# Amp.net
KiCad netlist of a schematic drawn in Altium Designer
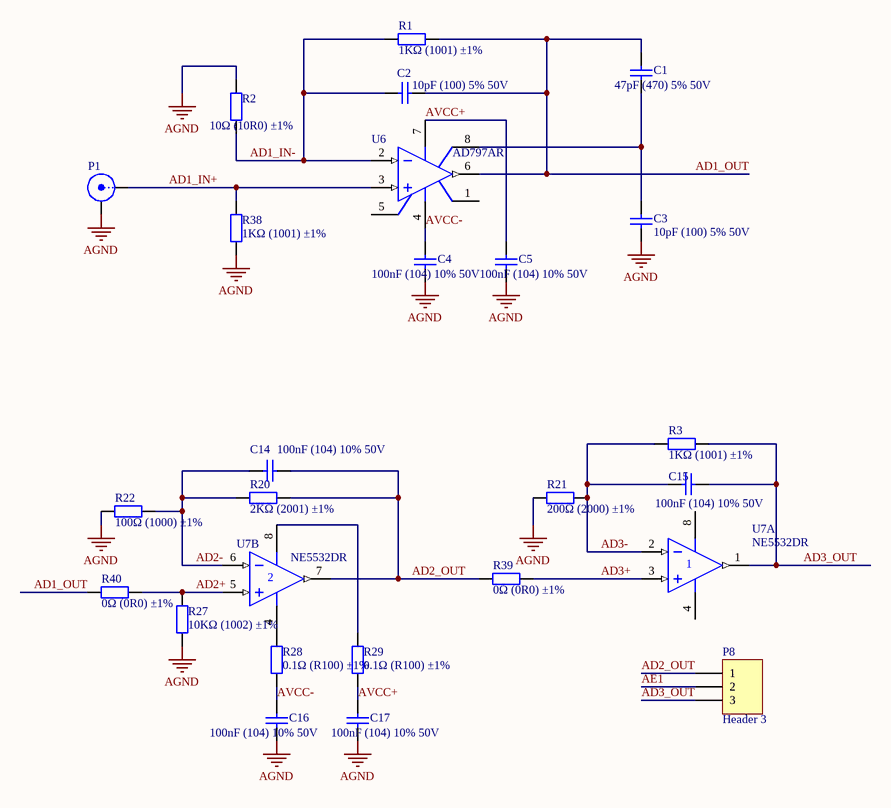
[diagram p0: Amp.SchDoc]

(export (version "E")
  (design (tool "Eeschema 10.0.6"))
  (components
    (comp (ref "C1")
      (value "47pF (470) 5% 50V")
      (footprint "0603_C")
      (description "贴片电容")
      (libsource (lib "Miscellaneous Devices LC") (part "0603 47pF (470) 5% 50V"))
    )
    (comp (ref "C2")
      (value "10pF (100) 5% 50V")
      (footprint "0603_C")
      (description "贴片电容")
      (libsource (lib "Miscellaneous Devices LC") (part "0603 10pF (100) 5% 50V"))
    )
    (comp (ref "C3")
      (value "10pF (100) 5% 50V")
      (footprint "0603_C")
      (description "贴片电容")
      (libsource (lib "Miscellaneous Devices LC") (part "0603 10pF (100) 5% 50V"))
    )
    (comp (ref "C4")
      (value "100nF (104) 10% 50V")
      (footprint "0603_C")
      (description "贴片电容")
      (libsource (lib "Miscellaneous Devices LC") (part "0603 100nF (104) 10% 50V"))
    )
    (comp (ref "C5")
      (value "100nF (104) 10% 50V")
      (footprint "0603_C")
      (description "贴片电容")
      (libsource (lib "Miscellaneous Devices LC") (part "0603 100nF (104) 10% 50V"))
    )
    (comp (ref "C14")
      (value "100nF (104) 10% 50V")
      (footprint "0603_C")
      (description "贴片电容")
      (libsource (lib "Miscellaneous Devices LC") (part "0603 100nF (104) 10% 50V"))
    )
    (comp (ref "C15")
      (value "100nF (104) 10% 50V")
      (footprint "0603_C")
      (description "贴片电容")
      (libsource (lib "Miscellaneous Devices LC") (part "0603 100nF (104) 10% 50V"))
    )
    (comp (ref "C16")
      (value "100nF (104) 10% 50V")
      (footprint "0603_C")
      (description "贴片电容")
      (libsource (lib "Miscellaneous Devices LC") (part "0603 100nF (104) 10% 50V"))
    )
    (comp (ref "C17")
      (value "100nF (104) 10% 50V")
      (footprint "0603_C")
      (description "贴片电容")
      (libsource (lib "Miscellaneous Devices LC") (part "0603 100nF (104) 10% 50V"))
    )
    (comp (ref "P1")
      (value "SMB")
      (footprint "SMB_V-RJ45")
      (description "SMB Straight Connector")
      (fields (field (name "PUBLISHER") "Altium Limited"))
      (libsource (lib "Miscellaneous Connectors") (part "SMB"))
    )
    (comp (ref "P8")
      (value "Header 3")
      (footprint "HDR1X3")
      (description "Header, 3-Pin")
      (fields (field (name "PUBLISHER") "Altium Limited"))
      (libsource (lib "Miscellaneous Connectors") (part "Header 3"))
    )
    (comp (ref "R1")
      (value "1KΩ (1001) ±1%")
      (footprint "0603_R")
      (description "贴片电阻")
      (libsource (lib "") (part "0603 1KΩ (1001) 1%_1"))
    )
    (comp (ref "R2")
      (value "10Ω (10R0) ±1%")
      (footprint "0603_R")
      (description "贴片电阻")
      (libsource (lib "Miscellaneous Devices LC") (part "0603 10Ω (10R0) 1%"))
    )
    (comp (ref "R3")
      (value "1KΩ (1001) ±1%")
      (footprint "0603_R")
      (description "贴片电阻")
      (libsource (lib "Miscellaneous Devices LC") (part "0603 1KΩ (1001) 1%"))
    )
    (comp (ref "R20")
      (value "2KΩ (2001) ±1%")
      (footprint "0603_R")
      (description "贴片电阻")
      (libsource (lib "Miscellaneous Devices LC") (part "0603 2KΩ (2001) 1%"))
    )
    (comp (ref "R21")
      (value "200Ω (2000) ±1%")
      (footprint "0603_R")
      (description "贴片电阻")
      (libsource (lib "Miscellaneous Devices LC") (part "0603 200Ω (2000) 1%"))
    )
    (comp (ref "R22")
      (value "100Ω (1000) ±1%")
      (footprint "0603_R")
      (description "贴片电阻")
      (libsource (lib "Miscellaneous Devices LC") (part "0603 100Ω (1000) 1%"))
    )
    (comp (ref "R27")
      (value "10KΩ (1002) ±1%")
      (footprint "0603_R")
      (description "贴片电阻")
      (libsource (lib "Miscellaneous Devices LC") (part "0603 10KΩ (1002) 1%"))
    )
    (comp (ref "R28")
      (value "0.1Ω (R100) ±1%")
      (footprint "1206_R")
      (description "贴片电阻")
      (libsource (lib "Miscellaneous Devices LC") (part "1206 0.1Ω (R100) 1%"))
    )
    (comp (ref "R29")
      (value "0.1Ω (R100) ±1%")
      (footprint "1206_R")
      (description "贴片电阻")
      (libsource (lib "Miscellaneous Devices LC") (part "1206 0.1Ω (R100) 1%"))
    )
    (comp (ref "R38")
      (value "1KΩ (1001) ±1%")
      (footprint "0603_R")
      (description "贴片电阻")
      (libsource (lib "") (part "0603 1KΩ (1001) 1%_2"))
    )
    (comp (ref "R39")
      (value "0Ω (0R0) ±1%")
      (footprint "0603_R")
      (description "贴片电阻")
      (libsource (lib "Miscellaneous Devices LC") (part "0603 0Ω (0R0) 1%"))
    )
    (comp (ref "R40")
      (value "0Ω (0R0) ±1%")
      (footprint "0603_R")
      (description "贴片电阻")
      (libsource (lib "Miscellaneous Devices LC") (part "0603 0Ω (0R0) 1%"))
    )
    (comp (ref "U6")
      (value "AD797AR")
      (footprint "SO-8C_N")
      (description "Ultra-Low Distortion, Ultra-Low Noise Operational Amplifier")
      (fields (field (name "PUBLISHER") "Altium Limited"))
      (libsource (lib "AD Operational Amplifier") (part "AD797AR"))
    )
    (comp (ref "U7")
      (value "NE5532DR")
      (footprint "SOIC-8_150mil")
      (description "功放")
      (libsource (lib "Miscellaneous Devices LC") (part "NE5532DR_[C7426]"))
    )
  )
  (nets
    (net (code "1") (name "/AD1_IN+") (class "Default")
      (node (ref "P1") (pin "1") (pinfunction "X_1") (pintype "passive"))
      (node (ref "R38") (pin "2") (pinfunction "2_2") (pintype "passive"))
      (node (ref "U6") (pin "3") (pinfunction "IN+_3") (pintype "input"))
    )
    (net (code "2") (name "/AD1_IN-") (class "Default")
      (node (ref "C2") (pin "2") (pinfunction "2_2") (pintype "passive"))
      (node (ref "R1") (pin "2") (pinfunction "2_2") (pintype "passive"))
      (node (ref "R2") (pin "1") (pinfunction "1_1") (pintype "passive"))
      (node (ref "U6") (pin "2") (pinfunction "IN-_2") (pintype "input"))
    )
    (net (code "3") (name "/AD1_OUT") (class "Default")
      (node (ref "C1") (pin "2") (pinfunction "2_2") (pintype "passive"))
      (node (ref "C2") (pin "1") (pinfunction "1_1") (pintype "passive"))
      (node (ref "R1") (pin "1") (pinfunction "1_1") (pintype "passive"))
      (node (ref "R40") (pin "1") (pinfunction "1_1") (pintype "passive"))
      (node (ref "U6") (pin "6") (pinfunction "OUT_6") (pintype "output"))
    )
    (net (code "4") (name "/AD2+") (class "Default")
      (node (ref "R27") (pin "2") (pinfunction "2_2") (pintype "passive"))
      (node (ref "R40") (pin "2") (pinfunction "2_2") (pintype "passive"))
      (node (ref "U7") (pin "5") (pinfunction "IN+_5") (pintype "input"))
    )
    (net (code "5") (name "/AD2-") (class "Default")
      (node (ref "C14") (pin "1") (pinfunction "1_1") (pintype "passive"))
      (node (ref "R20") (pin "1") (pinfunction "1_1") (pintype "passive"))
      (node (ref "R22") (pin "2") (pinfunction "2_2") (pintype "passive"))
      (node (ref "U7") (pin "6") (pinfunction "IN-_6") (pintype "input"))
    )
    (net (code "6") (name "/AD2_OUT") (class "Default")
      (node (ref "C14") (pin "2") (pinfunction "2_2") (pintype "passive"))
      (node (ref "P8") (pin "1") (pinfunction "1_1") (pintype "passive"))
      (node (ref "R20") (pin "2") (pinfunction "2_2") (pintype "passive"))
      (node (ref "R39") (pin "1") (pinfunction "1_1") (pintype "passive"))
      (node (ref "U7") (pin "7") (pinfunction "OUT_7") (pintype "output"))
    )
    (net (code "7") (name "/AD3+") (class "Default")
      (node (ref "R39") (pin "2") (pinfunction "2_2") (pintype "passive"))
      (node (ref "U7") (pin "3") (pinfunction "IN+_3") (pintype "input"))
    )
    (net (code "8") (name "/AD3-") (class "Default")
      (node (ref "C15") (pin "1") (pinfunction "1_1") (pintype "passive"))
      (node (ref "R21") (pin "2") (pinfunction "2_2") (pintype "passive"))
      (node (ref "R3") (pin "1") (pinfunction "1_1") (pintype "passive"))
      (node (ref "U7") (pin "2") (pinfunction "IN-_2") (pintype "input"))
    )
    (net (code "9") (name "/AD3_OUT") (class "Default")
      (node (ref "C15") (pin "2") (pinfunction "2_2") (pintype "passive"))
      (node (ref "P8") (pin "3") (pinfunction "3_3") (pintype "passive"))
      (node (ref "R3") (pin "2") (pinfunction "2_2") (pintype "passive"))
      (node (ref "U7") (pin "1") (pinfunction "OUT_1") (pintype "output"))
    )
    (net (code "10") (name "/AE1") (class "Default")
      (node (ref "P8") (pin "2") (pinfunction "2_2") (pintype "passive"))
    )
    (net (code "11") (name "/AVCC+") (class "Default")
      (node (ref "C17") (pin "2") (pinfunction "2_2") (pintype "passive"))
      (node (ref "C5") (pin "2") (pinfunction "2_2") (pintype "passive"))
      (node (ref "R29") (pin "1") (pinfunction "1_1") (pintype "passive"))
      (node (ref "U6") (pin "7") (pinfunction "V+_7") (pintype "power_in"))
    )
    (net (code "12") (name "/AVCC-") (class "Default")
      (node (ref "C16") (pin "2") (pinfunction "2_2") (pintype "passive"))
      (node (ref "C4") (pin "2") (pinfunction "2_2") (pintype "passive"))
      (node (ref "R28") (pin "1") (pinfunction "1_1") (pintype "passive"))
      (node (ref "U6") (pin "4") (pinfunction "V-_4") (pintype "power_in"))
    )
    (net (code "13") (name "AGND") (class "Default")
      (node (ref "C16") (pin "1") (pinfunction "1_1") (pintype "passive"))
      (node (ref "C17") (pin "1") (pinfunction "1_1") (pintype "passive"))
      (node (ref "C3") (pin "1") (pinfunction "1_1") (pintype "passive"))
      (node (ref "C4") (pin "1") (pinfunction "1_1") (pintype "passive"))
      (node (ref "C5") (pin "1") (pinfunction "1_1") (pintype "passive"))
      (node (ref "P1") (pin "2") (pinfunction "Y_2") (pintype "passive"))
      (node (ref "R2") (pin "2") (pinfunction "2_2") (pintype "passive"))
      (node (ref "R21") (pin "1") (pinfunction "1_1") (pintype "passive"))
      (node (ref "R22") (pin "1") (pinfunction "1_1") (pintype "passive"))
      (node (ref "R27") (pin "1") (pinfunction "1_1") (pintype "passive"))
      (node (ref "R38") (pin "1") (pinfunction "1_1") (pintype "passive"))
    )
    (net (code "14") (name "Net-(U6-DECMPEN)") (class "Default")
      (node (ref "C1") (pin "1") (pinfunction "1_1") (pintype "passive"))
      (node (ref "C3") (pin "2") (pinfunction "2_2") (pintype "passive"))
      (node (ref "U6") (pin "8") (pinfunction "DECMPEN_8") (pintype "passive"))
    )
    (net (code "15") (name "Net-(U7B-V+)") (class "Default")
      (node (ref "R29") (pin "2") (pinfunction "2_2") (pintype "passive"))
      (node (ref "U7") (pin "8") (pinfunction "V+_8") (pintype "power_in"))
    )
    (net (code "16") (name "Net-(U7B-V-)") (class "Default")
      (node (ref "R28") (pin "2") (pinfunction "2_2") (pintype "passive"))
      (node (ref "U7") (pin "4") (pinfunction "V-_4") (pintype "power_in"))
    )
    (net (code "17") (name "unconnected-(U6-OS_NUL-Pad1)") (class "Default")
      (node (ref "U6") (pin "1") (pinfunction "OS_NUL_1") (pintype "passive"))
    )
    (net (code "18") (name "unconnected-(U6-OS_NUL-Pad5)") (class "Default")
      (node (ref "U6") (pin "5") (pinfunction "OS_NUL_5") (pintype "passive"))
    )
    (net (code "19") (name "unconnected-(U7A-V+-Pad8)") (class "Default")
      (node (ref "U7") (pin "8") (pinfunction "V+_8") (pintype "power_in"))
    )
    (net (code "20") (name "unconnected-(U7A-V--Pad4)") (class "Default")
      (node (ref "U7") (pin "4") (pinfunction "V-_4") (pintype "power_in"))
    )
  )
)
